# ARM_DIL__Platine.net
KiCad netlist of a schematic drawn in Altium Designer
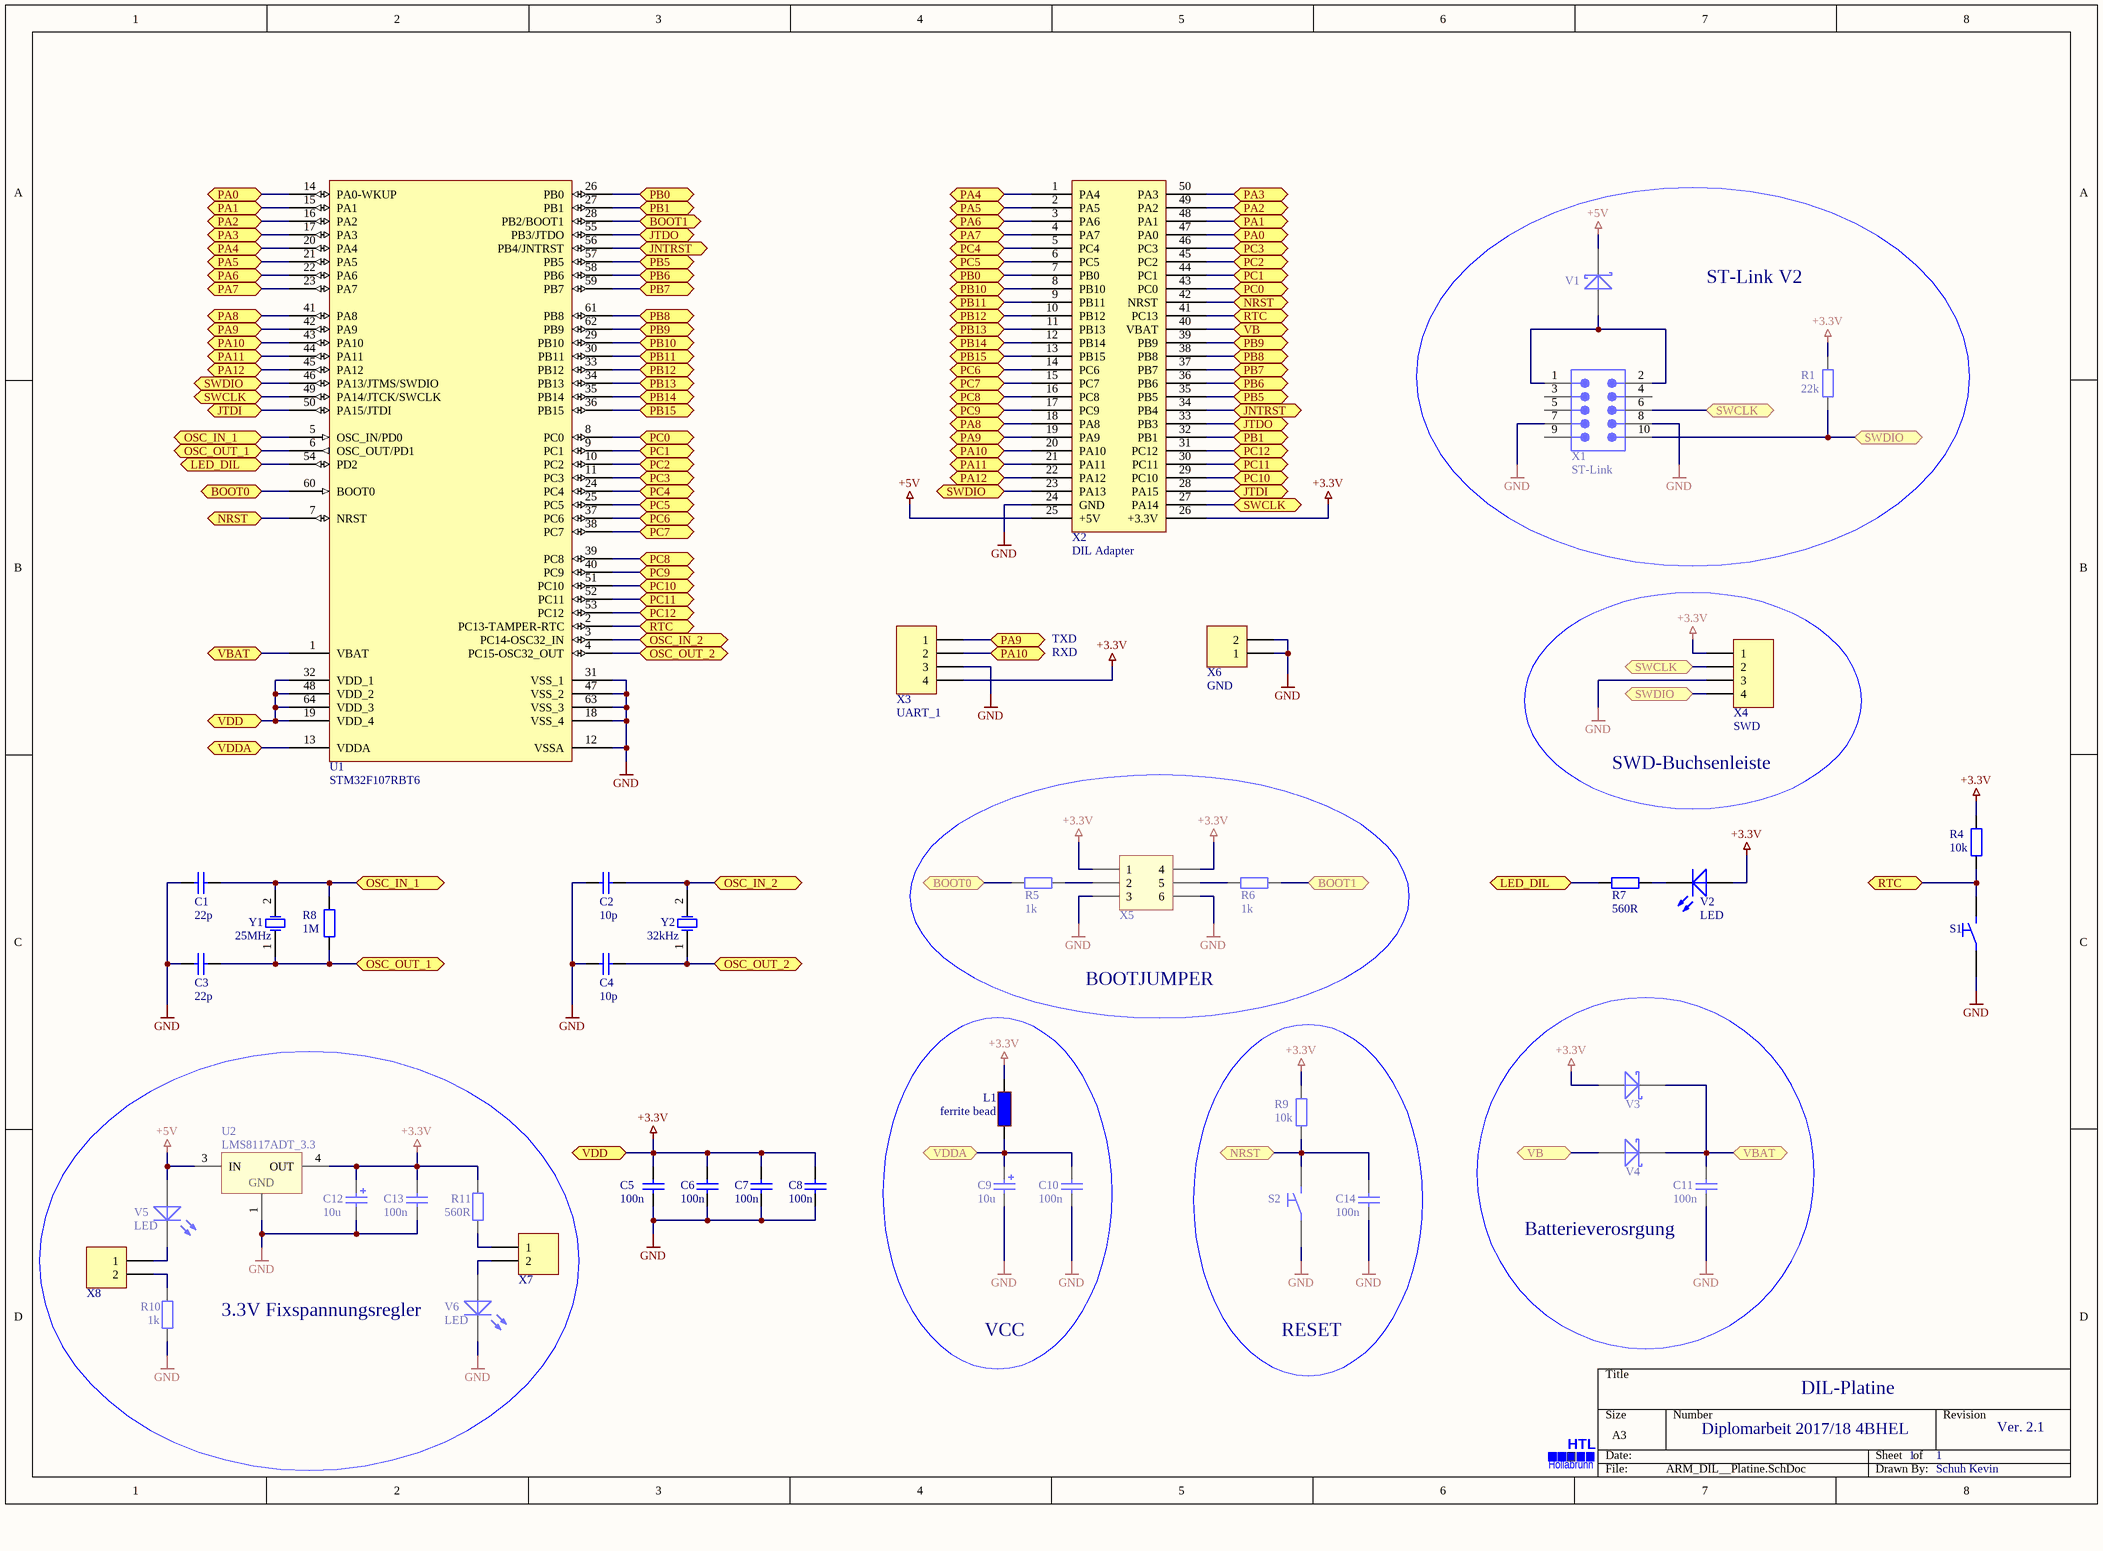
[diagram p0: ARM_DIL__Platine.SchDoc]

(export (version "E")
  (design (tool "Eeschema 10.0.6"))
  (components
    (comp (ref "C1")
      (value "22p")
      (footprint "0805_CAP")
      (description "Capacitor")
      (fields (field (name "Comment") "Cap") (field (name "PUBLISHER") "Altium Limited"))
      (libsource (lib "ARM_Libary_DIL") (part "Cap"))
    )
    (comp (ref "C2")
      (value "10p")
      (footprint "0805_CAP")
      (description "Capacitor")
      (fields (field (name "Comment") "Cap") (field (name "PUBLISHER") "Altium Limited"))
      (libsource (lib "ARM_Libary_DIL") (part "Cap"))
    )
    (comp (ref "C3")
      (value "22p")
      (footprint "0805_CAP")
      (description "Capacitor")
      (fields (field (name "Comment") "Cap") (field (name "PUBLISHER") "Altium Limited"))
      (libsource (lib "ARM_Libary_DIL") (part "Cap"))
    )
    (comp (ref "C4")
      (value "10p")
      (footprint "0805_CAP")
      (description "Capacitor")
      (fields (field (name "Comment") "Cap") (field (name "PUBLISHER") "Altium Limited"))
      (libsource (lib "ARM_Libary_DIL") (part "Cap"))
    )
    (comp (ref "C5")
      (value "100n")
      (footprint "0805_CAP")
      (description "Capacitor")
      (fields (field (name "Comment") "Cap") (field (name "PUBLISHER") "Altium Limited"))
      (libsource (lib "ARM_Libary_DIL") (part "Cap"))
    )
    (comp (ref "C6")
      (value "100n")
      (footprint "0805_CAP")
      (description "Capacitor")
      (fields (field (name "Comment") "Cap") (field (name "PUBLISHER") "Altium Limited"))
      (libsource (lib "ARM_Libary_DIL") (part "Cap"))
    )
    (comp (ref "C7")
      (value "100n")
      (footprint "0805_CAP")
      (description "Capacitor")
      (fields (field (name "Comment") "Cap") (field (name "PUBLISHER") "Altium Limited"))
      (libsource (lib "ARM_Libary_DIL") (part "Cap"))
    )
    (comp (ref "C8")
      (value "100n")
      (footprint "0805_CAP")
      (description "Capacitor")
      (fields (field (name "Comment") "Cap") (field (name "PUBLISHER") "Altium Limited"))
      (libsource (lib "ARM_Libary_DIL") (part "Cap"))
    )
    (comp (ref "C9")
      (value "10u")
      (footprint "1411_Cap_Pol")
      (description "Polarized Capacitor (Radial)")
      (fields (field (name "Comment") "Cap Pol") (field (name "PUBLISHER") "Altium Limited"))
      (libsource (lib "ARM_Libary_DIL") (part "Cap_Pol"))
    )
    (comp (ref "C10")
      (value "100n")
      (footprint "0805_CAP")
      (description "Capacitor")
      (fields (field (name "Comment") "Cap") (field (name "PUBLISHER") "Altium Limited"))
      (libsource (lib "ARM_Libary_DIL") (part "Cap"))
    )
    (comp (ref "C11")
      (value "100n")
      (footprint "0805_CAP")
      (description "Capacitor")
      (fields (field (name "Comment") "Cap") (field (name "PUBLISHER") "Altium Limited"))
      (libsource (lib "ARM_Libary_DIL") (part "Cap"))
    )
    (comp (ref "C12")
      (value "10u")
      (footprint "1411_Cap_Pol")
      (description "Polarized Capacitor (Radial)")
      (fields (field (name "Comment") "Cap Pol") (field (name "PUBLISHER") "Altium Limited"))
      (libsource (lib "ARM_Libary_DIL") (part "Cap_Pol"))
    )
    (comp (ref "C13")
      (value "100n")
      (footprint "0805_CAP")
      (description "Capacitor")
      (fields (field (name "Comment") "Cap") (field (name "PUBLISHER") "Altium Limited"))
      (libsource (lib "ARM_Libary_DIL") (part "Cap"))
    )
    (comp (ref "C14")
      (value "100n")
      (footprint "0805_CAP")
      (description "Capacitor")
      (fields (field (name "Comment") "Cap") (field (name "PUBLISHER") "Altium Limited"))
      (libsource (lib "ARM_Libary_DIL") (part "Cap"))
    )
    (comp (ref "L1")
      (value "ferrite bead")
      (footprint "0805_ferrit")
      (description "Inductor")
      (fields (field (name "PUBLISHER") "Altium Limited"))
      (libsource (lib "ARM_Libary_DIL") (part "Inductor"))
    )
    (comp (ref "Logo")
      (value "HTL Hollabrunn")
      (footprint "HTL_Logo")
      (libsource (lib "ARM_Libary_DIL") (part "HTL Logo"))
    )
    (comp (ref "R1")
      (value "22k")
      (footprint "0805_Res")
      (description "Resistor")
      (fields (field (name "Comment") "Res") (field (name "PUBLISHER") "Altium Limited"))
      (libsource (lib "ARM_Libary_DIL") (part "Res"))
    )
    (comp (ref "R4")
      (value "10k")
      (footprint "0805_Res")
      (description "Resistor")
      (fields (field (name "Comment") "Res") (field (name "PUBLISHER") "Altium Limited"))
      (libsource (lib "ARM_Libary_DIL") (part "Res"))
    )
    (comp (ref "R5")
      (value "1k")
      (footprint "0805_Res")
      (description "Resistor")
      (fields (field (name "Comment") "Res") (field (name "PUBLISHER") "Altium Limited"))
      (libsource (lib "") (part "Res_2"))
    )
    (comp (ref "R6")
      (value "1k")
      (footprint "0805_Res")
      (description "Resistor")
      (fields (field (name "Comment") "Res") (field (name "PUBLISHER") "Altium Limited"))
      (libsource (lib "") (part "Res_2"))
    )
    (comp (ref "R7")
      (value "560R")
      (footprint "0805_Res")
      (description "Resistor")
      (fields (field (name "Comment") "Res") (field (name "PUBLISHER") "Altium Limited"))
      (libsource (lib "") (part "Res_2"))
    )
    (comp (ref "R8")
      (value "1M")
      (footprint "0805_Res")
      (description "Resistor")
      (fields (field (name "Comment") "Res") (field (name "PUBLISHER") "Altium Limited"))
      (libsource (lib "ARM_Libary_DIL") (part "Res"))
    )
    (comp (ref "R9")
      (value "10k")
      (footprint "0805_Res")
      (description "Resistor")
      (fields (field (name "Comment") "Res") (field (name "PUBLISHER") "Altium Limited"))
      (libsource (lib "ARM_Libary_DIL") (part "Res"))
    )
    (comp (ref "R10")
      (value "1k")
      (footprint "0805_Res")
      (description "Resistor")
      (fields (field (name "Comment") "Res") (field (name "PUBLISHER") "Altium Limited"))
      (libsource (lib "ARM_Libary_DIL") (part "Res"))
    )
    (comp (ref "R11")
      (value "560R")
      (footprint "0805_Res")
      (description "Resistor")
      (fields (field (name "Comment") "Res") (field (name "PUBLISHER") "Altium Limited"))
      (libsource (lib "") (part "Res_1"))
    )
    (comp (ref "S1")
      (value "SW_SPST")
      (footprint "Printtaster")
      (description "Single-Pole, Single-Throw Switch")
      (fields (field (name "PUBLISHER") "Altium Limited"))
      (libsource (lib "ARM_Libary_DIL") (part "SW_SPST"))
    )
    (comp (ref "S2")
      (value "SW_SPST")
      (footprint "Printtaster")
      (description "Single-Pole, Single-Throw Switch")
      (fields (field (name "PUBLISHER") "Altium Limited"))
      (libsource (lib "ARM_Libary_DIL") (part "SW_SPST"))
    )
    (comp (ref "U1")
      (value "STM32F107RBT6")
      (footprint "STM32F103RBT6")
      (description "STM32 ARM-based 32-bit MCU with 128 Kbytes Flash, 64-pin LQFP, Industrial Temperature")
      (fields (field (name "PUBLISHER") "Altium Limited"))
      (libsource (lib "ARM_Libary_DIL") (part "STM32F103RBT6"))
    )
    (comp (ref "U2")
      (value "LMS8117ADT_3.3")
      (footprint "TD03B_N_Low_Dropout_Regulator")
      (description "1A Low-Dropout Linear Regulator")
      (fields
        (field (name "PARTNUMBER") "LMS8117ADT-3.3")
        (field (name "MANUFACTURER") "National Semiconductor")
        (field (name "PUBLISHER") "Altium Limited")
      )
      (libsource (lib "ARM_Libary_DIL") (part "LMS8117ADT_3.3"))
    )
    (comp (ref "V1")
      (value "D Schottky")
      (footprint "BAT254_Schottky")
      (description "Schottky Diode")
      (fields (field (name "PUBLISHER") "Altium Limited"))
      (libsource (lib "ARM_Libary_DIL") (part "D_Schottky"))
    )
    (comp (ref "V2")
      (value "LED")
      (footprint "0805_LED")
      (description "Typical RED, GREEN, YELLOW, AMBER GaAs LED")
      (fields (field (name "PUBLISHER") "Altium Limited"))
      (libsource (lib "ARM_Libary_DIL") (part "LED"))
    )
    (comp (ref "V3")
      (value "D Schottky")
      (footprint "BAT254_Schottky")
      (description "Schottky Diode")
      (fields (field (name "PUBLISHER") "Altium Limited"))
      (libsource (lib "ARM_Libary_DIL") (part "D_Schottky"))
    )
    (comp (ref "V4")
      (value "D Schottky")
      (footprint "BAT254_Schottky")
      (description "Schottky Diode")
      (fields (field (name "PUBLISHER") "Altium Limited"))
      (libsource (lib "ARM_Libary_DIL") (part "D_Schottky"))
    )
    (comp (ref "V5")
      (value "LED")
      (footprint "0805_LED")
      (description "Typical RED, GREEN, YELLOW, AMBER GaAs LED")
      (fields (field (name "PUBLISHER") "Altium Limited"))
      (libsource (lib "ARM_Libary_DIL") (part "LED"))
    )
    (comp (ref "V6")
      (value "LED")
      (footprint "0805_LED")
      (description "Typical RED, GREEN, YELLOW, AMBER GaAs LED")
      (fields (field (name "PUBLISHER") "Altium Limited"))
      (libsource (lib "ARM_Libary_DIL") (part "LED"))
    )
    (comp (ref "X1")
      (value "ST-Link")
      (footprint "HDR2X5_STLink")
      (fields (field (name "PUBLISHER") "Altium Limited"))
      (libsource (lib "ARM_Libary_DIL") (part "STLink"))
    )
    (comp (ref "X2")
      (value "DIL Adapter")
      (footprint "DIL_Adapter_V03")
      (description "DIL Adapter 50 Pin")
      (libsource (lib "ARM_Libary_DIL") (part "DIL_Adapter_V03"))
    )
    (comp (ref "X3")
      (value "UART_1")
      (footprint "HDR1X4_UART")
      (description "Header, 4-Pin")
      (fields (field (name "PUBLISHER") "Altium Limited"))
      (libsource (lib "ARM_Libary_DIL") (part "UART_1"))
    )
    (comp (ref "X4")
      (value "SWD")
      (footprint "HDR1X4_SWD")
      (description "Header, 4-Pin")
      (fields (field (name "PUBLISHER") "Altium Limited"))
      (libsource (lib "ARM_Libary_DIL") (part "SWD"))
    )
    (comp (ref "X5")
      (value "Header 3x2")
      (footprint "HDR2X3")
      (description "Header, 3-Pin, Dual row")
      (fields (field (name "PUBLISHER") "Altium Limited"))
      (libsource (lib "ARM_Libary_DIL") (part "Header 3x2"))
    )
    (comp (ref "X6")
      (value "GND")
      (footprint "HDR1X2")
      (description "Header, 2-Pin")
      (fields (field (name "PUBLISHER") "Altium Limited"))
      (libsource (lib "") (part "Header_2_1"))
    )
    (comp (ref "X7")
      (value "~")
      (footprint "HDR1X2")
      (description "Header, 2-Pin")
      (fields (field (name "PUBLISHER") "Altium Limited"))
      (libsource (lib "ARM_Libary_DIL") (part "Header_2"))
    )
    (comp (ref "X8")
      (value "~")
      (footprint "HDR1X2")
      (description "Header, 2-Pin")
      (fields (field (name "PUBLISHER") "Altium Limited"))
      (libsource (lib "") (part "Header_2_2"))
    )
    (comp (ref "Y1")
      (value "25MHz")
      (footprint "Schwingquarz_8MHz_TOP")
      (description "Surface Mount Quartz Crystal")
      (fields (field (name "PUBLISHER") "Altium Limited"))
      (libsource (lib "ARM_Libary_DIL") (part "3SMXA"))
    )
    (comp (ref "Y2")
      (value "32kHz")
      (footprint "Schwingquarz_32k")
      (description "Surface Mount Quartz Crystal")
      (fields (field (name "PUBLISHER") "Altium Limited"))
      (libsource (lib "ARM_Libary_DIL") (part "3SMXA"))
    )
  )
  (nets
    (net (code "1") (name "+3.3V") (class "Default")
      (node (ref "C12") (pin "1") (pinfunction "1_1") (pintype "passive"))
      (node (ref "C13") (pin "2") (pinfunction "2_2") (pintype "passive"))
      (node (ref "C5") (pin "2") (pinfunction "2_2") (pintype "passive"))
      (node (ref "C6") (pin "2") (pinfunction "2_2") (pintype "passive"))
      (node (ref "C7") (pin "2") (pinfunction "2_2") (pintype "passive"))
      (node (ref "C8") (pin "2") (pinfunction "2_2") (pintype "passive"))
      (node (ref "L1") (pin "2") (pinfunction "2_2") (pintype "passive"))
      (node (ref "R1") (pin "2") (pinfunction "2_2") (pintype "passive"))
      (node (ref "R11") (pin "1") (pinfunction "1_1") (pintype "passive"))
      (node (ref "R4") (pin "2") (pinfunction "2_2") (pintype "passive"))
      (node (ref "R9") (pin "2") (pinfunction "2_2") (pintype "passive"))
      (node (ref "U1") (pin "19") (pinfunction "VDD_4_19") (pintype "power_in"))
      (node (ref "U1") (pin "32") (pinfunction "VDD_1_32") (pintype "power_in"))
      (node (ref "U1") (pin "48") (pinfunction "VDD_2_48") (pintype "power_in"))
      (node (ref "U1") (pin "64") (pinfunction "VDD_3_64") (pintype "power_in"))
      (node (ref "U2") (pin "4") (pinfunction "OUT_4") (pintype "power_in"))
      (node (ref "V2") (pin "1") (pinfunction "A_1") (pintype "passive"))
      (node (ref "V3") (pin "1") (pinfunction "A_1") (pintype "passive"))
      (node (ref "X2") (pin "26") (pinfunction "+3.3V_26") (pintype "passive"))
      (node (ref "X3") (pin "4") (pinfunction "4_4") (pintype "passive"))
      (node (ref "X4") (pin "1") (pinfunction "1_1") (pintype "passive"))
      (node (ref "X5") (pin "1") (pinfunction "1_1") (pintype "passive"))
      (node (ref "X5") (pin "4") (pinfunction "4_4") (pintype "passive"))
    )
    (net (code "2") (name "+5V") (class "Default")
      (node (ref "U2") (pin "3") (pinfunction "IN_3") (pintype "power_in"))
      (node (ref "V1") (pin "2") (pinfunction "K_2") (pintype "passive"))
      (node (ref "V5") (pin "1") (pinfunction "A_1") (pintype "passive"))
      (node (ref "X2") (pin "25") (pinfunction "+5V_25") (pintype "passive"))
    )
    (net (code "3") (name "/BOOT0") (class "Default")
      (node (ref "R5") (pin "2") (pinfunction "2_2") (pintype "passive"))
      (node (ref "U1") (pin "60") (pinfunction "BOOT0_60") (pintype "input"))
    )
    (net (code "4") (name "/BOOT1") (class "Default")
      (node (ref "R6") (pin "1") (pinfunction "1_1") (pintype "passive"))
      (node (ref "U1") (pin "28") (pinfunction "PB2/BOOT1_28") (pintype "bidirectional"))
    )
    (net (code "5") (name "/JNTRST") (class "Default")
      (node (ref "U1") (pin "56") (pinfunction "PB4/JNTRST_56") (pintype "bidirectional"))
      (node (ref "X2") (pin "34") (pinfunction "PB4_34") (pintype "passive"))
    )
    (net (code "6") (name "/JTDI") (class "Default")
      (node (ref "U1") (pin "50") (pinfunction "PA15/JTDI_50") (pintype "bidirectional"))
      (node (ref "X2") (pin "28") (pinfunction "PA15_28") (pintype "passive"))
    )
    (net (code "7") (name "/JTDO") (class "Default")
      (node (ref "U1") (pin "55") (pinfunction "PB3/JTDO_55") (pintype "bidirectional"))
      (node (ref "X2") (pin "33") (pinfunction "PB3_33") (pintype "passive"))
    )
    (net (code "8") (name "/LED_DIL") (class "Default")
      (node (ref "R7") (pin "2") (pinfunction "2_2") (pintype "passive"))
      (node (ref "U1") (pin "54") (pinfunction "PD2_54") (pintype "bidirectional"))
    )
    (net (code "9") (name "/NRST") (class "Default")
      (node (ref "C14") (pin "2") (pinfunction "2_2") (pintype "passive"))
      (node (ref "R9") (pin "1") (pinfunction "1_1") (pintype "passive"))
      (node (ref "S2") (pin "2") (pinfunction "NO_2") (pintype "passive"))
      (node (ref "U1") (pin "7") (pinfunction "NRST_7") (pintype "bidirectional"))
      (node (ref "X2") (pin "42") (pinfunction "NRST_42") (pintype "passive"))
    )
    (net (code "10") (name "/OSC_IN_1") (class "Default")
      (node (ref "C1") (pin "2") (pinfunction "2_2") (pintype "passive"))
      (node (ref "R8") (pin "2") (pinfunction "2_2") (pintype "passive"))
      (node (ref "U1") (pin "5") (pinfunction "OSC_IN/PD0_5") (pintype "input"))
      (node (ref "Y1") (pin "2") (pinfunction "OSC2_2") (pintype "passive"))
    )
    (net (code "11") (name "/OSC_IN_2") (class "Default")
      (node (ref "C2") (pin "2") (pinfunction "2_2") (pintype "passive"))
      (node (ref "U1") (pin "3") (pinfunction "PC14-OSC32_IN_3") (pintype "bidirectional"))
      (node (ref "Y2") (pin "2") (pinfunction "OSC2_2") (pintype "passive"))
    )
    (net (code "12") (name "/OSC_OUT_1") (class "Default")
      (node (ref "C3") (pin "1") (pinfunction "1_1") (pintype "passive"))
      (node (ref "R8") (pin "1") (pinfunction "1_1") (pintype "passive"))
      (node (ref "U1") (pin "6") (pinfunction "OSC_OUT/PD1_6") (pintype "output"))
      (node (ref "Y1") (pin "1") (pinfunction "OSC1_1") (pintype "passive"))
    )
    (net (code "13") (name "/OSC_OUT_2") (class "Default")
      (node (ref "C4") (pin "1") (pinfunction "1_1") (pintype "passive"))
      (node (ref "U1") (pin "4") (pinfunction "PC15-OSC32_OUT_4") (pintype "bidirectional"))
      (node (ref "Y2") (pin "1") (pinfunction "OSC1_1") (pintype "passive"))
    )
    (net (code "14") (name "/PA0") (class "Default")
      (node (ref "U1") (pin "14") (pinfunction "PA0-WKUP_14") (pintype "bidirectional"))
      (node (ref "X2") (pin "47") (pinfunction "PA0_47") (pintype "passive"))
    )
    (net (code "15") (name "/PA1") (class "Default")
      (node (ref "U1") (pin "15") (pinfunction "PA1_15") (pintype "bidirectional"))
      (node (ref "X2") (pin "48") (pinfunction "PA1_48") (pintype "passive"))
    )
    (net (code "16") (name "/PA2") (class "Default")
      (node (ref "U1") (pin "16") (pinfunction "PA2_16") (pintype "bidirectional"))
      (node (ref "X2") (pin "49") (pinfunction "PA2_49") (pintype "passive"))
    )
    (net (code "17") (name "/PA3") (class "Default")
      (node (ref "U1") (pin "17") (pinfunction "PA3_17") (pintype "bidirectional"))
      (node (ref "X2") (pin "50") (pinfunction "PA3_50") (pintype "passive"))
    )
    (net (code "18") (name "/PA4") (class "Default")
      (node (ref "U1") (pin "20") (pinfunction "PA4_20") (pintype "bidirectional"))
      (node (ref "X2") (pin "1") (pinfunction "PA4_1") (pintype "passive"))
    )
    (net (code "19") (name "/PA5") (class "Default")
      (node (ref "U1") (pin "21") (pinfunction "PA5_21") (pintype "bidirectional"))
      (node (ref "X2") (pin "2") (pinfunction "PA5_2") (pintype "passive"))
    )
    (net (code "20") (name "/PA6") (class "Default")
      (node (ref "U1") (pin "22") (pinfunction "PA6_22") (pintype "bidirectional"))
      (node (ref "X2") (pin "3") (pinfunction "PA6_3") (pintype "passive"))
    )
    (net (code "21") (name "/PA7") (class "Default")
      (node (ref "U1") (pin "23") (pinfunction "PA7_23") (pintype "bidirectional"))
      (node (ref "X2") (pin "4") (pinfunction "PA7_4") (pintype "passive"))
    )
    (net (code "22") (name "/PA8") (class "Default")
      (node (ref "U1") (pin "41") (pinfunction "PA8_41") (pintype "bidirectional"))
      (node (ref "X2") (pin "18") (pinfunction "PA8_18") (pintype "passive"))
    )
    (net (code "23") (name "/PA9") (class "Default")
      (node (ref "U1") (pin "42") (pinfunction "PA9_42") (pintype "bidirectional"))
      (node (ref "X2") (pin "19") (pinfunction "PA9_19") (pintype "passive"))
      (node (ref "X3") (pin "1") (pinfunction "1_1") (pintype "passive"))
    )
    (net (code "24") (name "/PA10") (class "Default")
      (node (ref "U1") (pin "43") (pinfunction "PA10_43") (pintype "bidirectional"))
      (node (ref "X2") (pin "20") (pinfunction "PA10_20") (pintype "passive"))
      (node (ref "X3") (pin "2") (pinfunction "2_2") (pintype "passive"))
    )
    (net (code "25") (name "/PA11") (class "Default")
      (node (ref "U1") (pin "44") (pinfunction "PA11_44") (pintype "bidirectional"))
      (node (ref "X2") (pin "21") (pinfunction "PA11_21") (pintype "passive"))
    )
    (net (code "26") (name "/PA12") (class "Default")
      (node (ref "U1") (pin "45") (pinfunction "PA12_45") (pintype "bidirectional"))
      (node (ref "X2") (pin "22") (pinfunction "PA12_22") (pintype "passive"))
    )
    (net (code "27") (name "/PB0") (class "Default")
      (node (ref "U1") (pin "26") (pinfunction "PB0_26") (pintype "bidirectional"))
      (node (ref "X2") (pin "7") (pinfunction "PB0_7") (pintype "passive"))
    )
    (net (code "28") (name "/PB1") (class "Default")
      (node (ref "U1") (pin "27") (pinfunction "PB1_27") (pintype "bidirectional"))
      (node (ref "X2") (pin "32") (pinfunction "PB1_32") (pintype "passive"))
    )
    (net (code "29") (name "/PB5") (class "Default")
      (node (ref "U1") (pin "57") (pinfunction "PB5_57") (pintype "bidirectional"))
      (node (ref "X2") (pin "35") (pinfunction "PB5_35") (pintype "passive"))
    )
    (net (code "30") (name "/PB6") (class "Default")
      (node (ref "U1") (pin "58") (pinfunction "PB6_58") (pintype "bidirectional"))
      (node (ref "X2") (pin "36") (pinfunction "PB6_36") (pintype "passive"))
    )
    (net (code "31") (name "/PB7") (class "Default")
      (node (ref "U1") (pin "59") (pinfunction "PB7_59") (pintype "bidirectional"))
      (node (ref "X2") (pin "37") (pinfunction "PB7_37") (pintype "passive"))
    )
    (net (code "32") (name "/PB8") (class "Default")
      (node (ref "U1") (pin "61") (pinfunction "PB8_61") (pintype "bidirectional"))
      (node (ref "X2") (pin "38") (pinfunction "PB8_38") (pintype "passive"))
    )
    (net (code "33") (name "/PB9") (class "Default")
      (node (ref "U1") (pin "62") (pinfunction "PB9_62") (pintype "bidirectional"))
      (node (ref "X2") (pin "39") (pinfunction "PB9_39") (pintype "passive"))
    )
    (net (code "34") (name "/PB10") (class "Default")
      (node (ref "U1") (pin "29") (pinfunction "PB10_29") (pintype "bidirectional"))
      (node (ref "X2") (pin "8") (pinfunction "PB10_8") (pintype "passive"))
    )
    (net (code "35") (name "/PB11") (class "Default")
      (node (ref "U1") (pin "30") (pinfunction "PB11_30") (pintype "bidirectional"))
      (node (ref "X2") (pin "9") (pinfunction "PB11_9") (pintype "passive"))
    )
    (net (code "36") (name "/PB12") (class "Default")
      (node (ref "U1") (pin "33") (pinfunction "PB12_33") (pintype "bidirectional"))
      (node (ref "X2") (pin "10") (pinfunction "PB12_10") (pintype "passive"))
    )
    (net (code "37") (name "/PB13") (class "Default")
      (node (ref "U1") (pin "34") (pinfunction "PB13_34") (pintype "bidirectional"))
      (node (ref "X2") (pin "11") (pinfunction "PB13_11") (pintype "passive"))
    )
    (net (code "38") (name "/PB14") (class "Default")
      (node (ref "U1") (pin "35") (pinfunction "PB14_35") (pintype "bidirectional"))
      (node (ref "X2") (pin "12") (pinfunction "PB14_12") (pintype "passive"))
    )
    (net (code "39") (name "/PB15") (class "Default")
      (node (ref "U1") (pin "36") (pinfunction "PB15_36") (pintype "bidirectional"))
      (node (ref "X2") (pin "13") (pinfunction "PB15_13") (pintype "passive"))
    )
    (net (code "40") (name "/PC0") (class "Default")
      (node (ref "U1") (pin "8") (pinfunction "PC0_8") (pintype "bidirectional"))
      (node (ref "X2") (pin "43") (pinfunction "PC0_43") (pintype "passive"))
    )
    (net (code "41") (name "/PC1") (class "Default")
      (node (ref "U1") (pin "9") (pinfunction "PC1_9") (pintype "bidirectional"))
      (node (ref "X2") (pin "44") (pinfunction "PC1_44") (pintype "passive"))
    )
    (net (code "42") (name "/PC2") (class "Default")
      (node (ref "U1") (pin "10") (pinfunction "PC2_10") (pintype "bidirectional"))
      (node (ref "X2") (pin "45") (pinfunction "PC2_45") (pintype "passive"))
    )
    (net (code "43") (name "/PC3") (class "Default")
      (node (ref "U1") (pin "11") (pinfunction "PC3_11") (pintype "bidirectional"))
      (node (ref "X2") (pin "46") (pinfunction "PC3_46") (pintype "passive"))
    )
    (net (code "44") (name "/PC4") (class "Default")
      (node (ref "U1") (pin "24") (pinfunction "PC4_24") (pintype "bidirectional"))
      (node (ref "X2") (pin "5") (pinfunction "PC4_5") (pintype "passive"))
    )
    (net (code "45") (name "/PC5") (class "Default")
      (node (ref "U1") (pin "25") (pinfunction "PC5_25") (pintype "bidirectional"))
      (node (ref "X2") (pin "6") (pinfunction "PC5_6") (pintype "passive"))
    )
    (net (code "46") (name "/PC6") (class "Default")
      (node (ref "U1") (pin "37") (pinfunction "PC6_37") (pintype "bidirectional"))
      (node (ref "X2") (pin "14") (pinfunction "PC6_14") (pintype "passive"))
    )
    (net (code "47") (name "/PC7") (class "Default")
      (node (ref "U1") (pin "38") (pinfunction "PC7_38") (pintype "bidirectional"))
      (node (ref "X2") (pin "15") (pinfunction "PC7_15") (pintype "passive"))
    )
    (net (code "48") (name "/PC8") (class "Default")
      (node (ref "U1") (pin "39") (pinfunction "PC8_39") (pintype "bidirectional"))
      (node (ref "X2") (pin "16") (pinfunction "PC8_16") (pintype "passive"))
    )
    (net (code "49") (name "/PC9") (class "Default")
      (node (ref "U1") (pin "40") (pinfunction "PC9_40") (pintype "bidirectional"))
      (node (ref "X2") (pin "17") (pinfunction "PC9_17") (pintype "passive"))
    )
    (net (code "50") (name "/PC10") (class "Default")
      (node (ref "U1") (pin "51") (pinfunction "PC10_51") (pintype "bidirectional"))
      (node (ref "X2") (pin "29") (pinfunction "PC10_29") (pintype "passive"))
    )
    (net (code "51") (name "/PC11") (class "Default")
      (node (ref "U1") (pin "52") (pinfunction "PC11_52") (pintype "bidirectional"))
      (node (ref "X2") (pin "30") (pinfunction "PC11_30") (pintype "passive"))
    )
    (net (code "52") (name "/PC12") (class "Default")
      (node (ref "U1") (pin "53") (pinfunction "PC12_53") (pintype "bidirectional"))
      (node (ref "X2") (pin "31") (pinfunction "PC12_31") (pintype "passive"))
    )
    (net (code "53") (name "/RTC") (class "Default")
      (node (ref "R4") (pin "1") (pinfunction "1_1") (pintype "passive"))
      (node (ref "S1") (pin "2") (pinfunction "NO_2") (pintype "passive"))
      (node (ref "U1") (pin "2") (pinfunction "PC13-TAMPER-RTC_2") (pintype "bidirectional"))
      (node (ref "X2") (pin "41") (pinfunction "PC13_41") (pintype "passive"))
    )
    (net (code "54") (name "/SWCLK") (class "Default")
      (node (ref "U1") (pin "49") (pinfunction "PA14/JTCK/SWCLK_49") (pintype "bidirectional"))
      (node (ref "X1") (pin "6") (pinfunction "6_6") (pintype "passive"))
      (node (ref "X2") (pin "27") (pinfunction "PA14_27") (pintype "passive"))
      (node (ref "X4") (pin "2") (pinfunction "2_2") (pintype "passive"))
    )
    (net (code "55") (name "/SWDIO") (class "Default")
      (node (ref "R1") (pin "1") (pinfunction "1_1") (pintype "passive"))
      (node (ref "U1") (pin "46") (pinfunction "PA13/JTMS/SWDIO_46") (pintype "bidirectional"))
      (node (ref "X1") (pin "10") (pinfunction "10_10") (pintype "passive"))
      (node (ref "X2") (pin "23") (pinfunction "PA13_23") (pintype "passive"))
      (node (ref "X4") (pin "4") (pinfunction "4_4") (pintype "passive"))
    )
    (net (code "56") (name "/VB") (class "Default")
      (node (ref "V4") (pin "1") (pinfunction "A_1") (pintype "passive"))
      (node (ref "X2") (pin "40") (pinfunction "VBAT_40") (pintype "passive"))
    )
    (net (code "57") (name "/VBAT") (class "Default")
      (node (ref "C11") (pin "2") (pinfunction "2_2") (pintype "passive"))
      (node (ref "U1") (pin "1") (pinfunction "VBAT_1") (pintype "power_in"))
      (node (ref "V3") (pin "2") (pinfunction "K_2") (pintype "passive"))
      (node (ref "V4") (pin "2") (pinfunction "K_2") (pintype "passive"))
    )
    (net (code "58") (name "/VDDA") (class "Default")
      (node (ref "C10") (pin "2") (pinfunction "2_2") (pintype "passive"))
      (node (ref "C9") (pin "1") (pinfunction "1_1") (pintype "passive"))
      (node (ref "L1") (pin "1") (pinfunction "1_1") (pintype "passive"))
      (node (ref "U1") (pin "13") (pinfunction "VDDA_13") (pintype "power_in"))
    )
    (net (code "59") (name "GND") (class "Default")
      (node (ref "C1") (pin "1") (pinfunction "1_1") (pintype "passive"))
      (node (ref "C10") (pin "1") (pinfunction "1_1") (pintype "passive"))
      (node (ref "C11") (pin "1") (pinfunction "1_1") (pintype "passive"))
      (node (ref "C12") (pin "2") (pinfunction "2_2") (pintype "passive"))
      (node (ref "C13") (pin "1") (pinfunction "1_1") (pintype "passive"))
      (node (ref "C14") (pin "1") (pinfunction "1_1") (pintype "passive"))
      (node (ref "C2") (pin "1") (pinfunction "1_1") (pintype "passive"))
      (node (ref "C3") (pin "2") (pinfunction "2_2") (pintype "passive"))
      (node (ref "C4") (pin "2") (pinfunction "2_2") (pintype "passive"))
      (node (ref "C5") (pin "1") (pinfunction "1_1") (pintype "passive"))
      (node (ref "C6") (pin "1") (pinfunction "1_1") (pintype "passive"))
      (node (ref "C7") (pin "1") (pinfunction "1_1") (pintype "passive"))
      (node (ref "C8") (pin "1") (pinfunction "1_1") (pintype "passive"))
      (node (ref "C9") (pin "2") (pinfunction "2_2") (pintype "passive"))
      (node (ref "R10") (pin "1") (pinfunction "1_1") (pintype "passive"))
      (node (ref "S1") (pin "1") (pinfunction "COMMON_1") (pintype "passive"))
      (node (ref "S2") (pin "1") (pinfunction "COMMON_1") (pintype "passive"))
      (node (ref "U1") (pin "12") (pinfunction "VSSA_12") (pintype "power_in"))
      (node (ref "U1") (pin "18") (pinfunction "VSS_4_18") (pintype "power_in"))
      (node (ref "U1") (pin "31") (pinfunction "VSS_1_31") (pintype "power_in"))
      (node (ref "U1") (pin "47") (pinfunction "VSS_2_47") (pintype "power_in"))
      (node (ref "U1") (pin "63") (pinfunction "VSS_3_63") (pintype "power_in"))
      (node (ref "U2") (pin "1") (pinfunction "GND_1") (pintype "power_in"))
      (node (ref "V6") (pin "2") (pinfunction "K_2") (pintype "passive"))
      (node (ref "X1") (pin "7") (pinfunction "7_7") (pintype "passive"))
      (node (ref "X1") (pin "8") (pinfunction "8_8") (pintype "passive"))
      (node (ref "X2") (pin "24") (pinfunction "GND_24") (pintype "passive"))
      (node (ref "X3") (pin "3") (pinfunction "3_3") (pintype "passive"))
      (node (ref "X4") (pin "3") (pinfunction "3_3") (pintype "passive"))
      (node (ref "X5") (pin "3") (pinfunction "3_3") (pintype "passive"))
      (node (ref "X5") (pin "6") (pinfunction "6_6") (pintype "passive"))
      (node (ref "X6") (pin "1") (pinfunction "1_1") (pintype "passive"))
      (node (ref "X6") (pin "2") (pinfunction "2_2") (pintype "passive"))
    )
    (net (code "60") (name "Net-(R5-Pad1)") (class "Default")
      (node (ref "R5") (pin "1") (pinfunction "1_1") (pintype "passive"))
      (node (ref "X5") (pin "2") (pinfunction "2_2") (pintype "passive"))
    )
    (net (code "61") (name "Net-(R6-Pad2)") (class "Default")
      (node (ref "R6") (pin "2") (pinfunction "2_2") (pintype "passive"))
      (node (ref "X5") (pin "5") (pinfunction "5_5") (pintype "passive"))
    )
    (net (code "62") (name "Net-(R10-Pad2)") (class "Default")
      (node (ref "R10") (pin "2") (pinfunction "2_2") (pintype "passive"))
      (node (ref "X8") (pin "2") (pinfunction "2_2") (pintype "passive"))
    )
    (net (code "63") (name "Net-(R11-Pad2)") (class "Default")
      (node (ref "R11") (pin "2") (pinfunction "2_2") (pintype "passive"))
      (node (ref "X7") (pin "1") (pinfunction "1_1") (pintype "passive"))
    )
    (net (code "64") (name "Net-(V1-A)") (class "Default")
      (node (ref "V1") (pin "1") (pinfunction "A_1") (pintype "passive"))
      (node (ref "X1") (pin "1") (pinfunction "1_1") (pintype "passive"))
      (node (ref "X1") (pin "2") (pinfunction "2_2") (pintype "passive"))
    )
    (net (code "65") (name "Net-(V2-K)") (class "Default")
      (node (ref "R7") (pin "1") (pinfunction "1_1") (pintype "passive"))
      (node (ref "V2") (pin "2") (pinfunction "K_2") (pintype "passive"))
    )
    (net (code "66") (name "Net-(V5-K)") (class "Default")
      (node (ref "V5") (pin "2") (pinfunction "K_2") (pintype "passive"))
      (node (ref "X8") (pin "1") (pinfunction "1_1") (pintype "passive"))
    )
    (net (code "67") (name "Net-(V6-A)") (class "Default")
      (node (ref "V6") (pin "1") (pinfunction "A_1") (pintype "passive"))
      (node (ref "X7") (pin "2") (pinfunction "2_2") (pintype "passive"))
    )
    (net (code "68") (name "unconnected-(X1-Pad3)") (class "Default")
      (node (ref "X1") (pin "3") (pinfunction "3_3") (pintype "passive"))
    )
    (net (code "69") (name "unconnected-(X1-Pad4)") (class "Default")
      (node (ref "X1") (pin "4") (pinfunction "4_4") (pintype "passive"))
    )
    (net (code "70") (name "unconnected-(X1-Pad5)") (class "Default")
      (node (ref "X1") (pin "5") (pinfunction "5_5") (pintype "passive"))
    )
    (net (code "71") (name "unconnected-(X1-Pad9)") (class "Default")
      (node (ref "X1") (pin "9") (pinfunction "9_9") (pintype "passive"))
    )
  )
)
